# van_pro.net
KiCad netlist of a schematic drawn in EAGLE
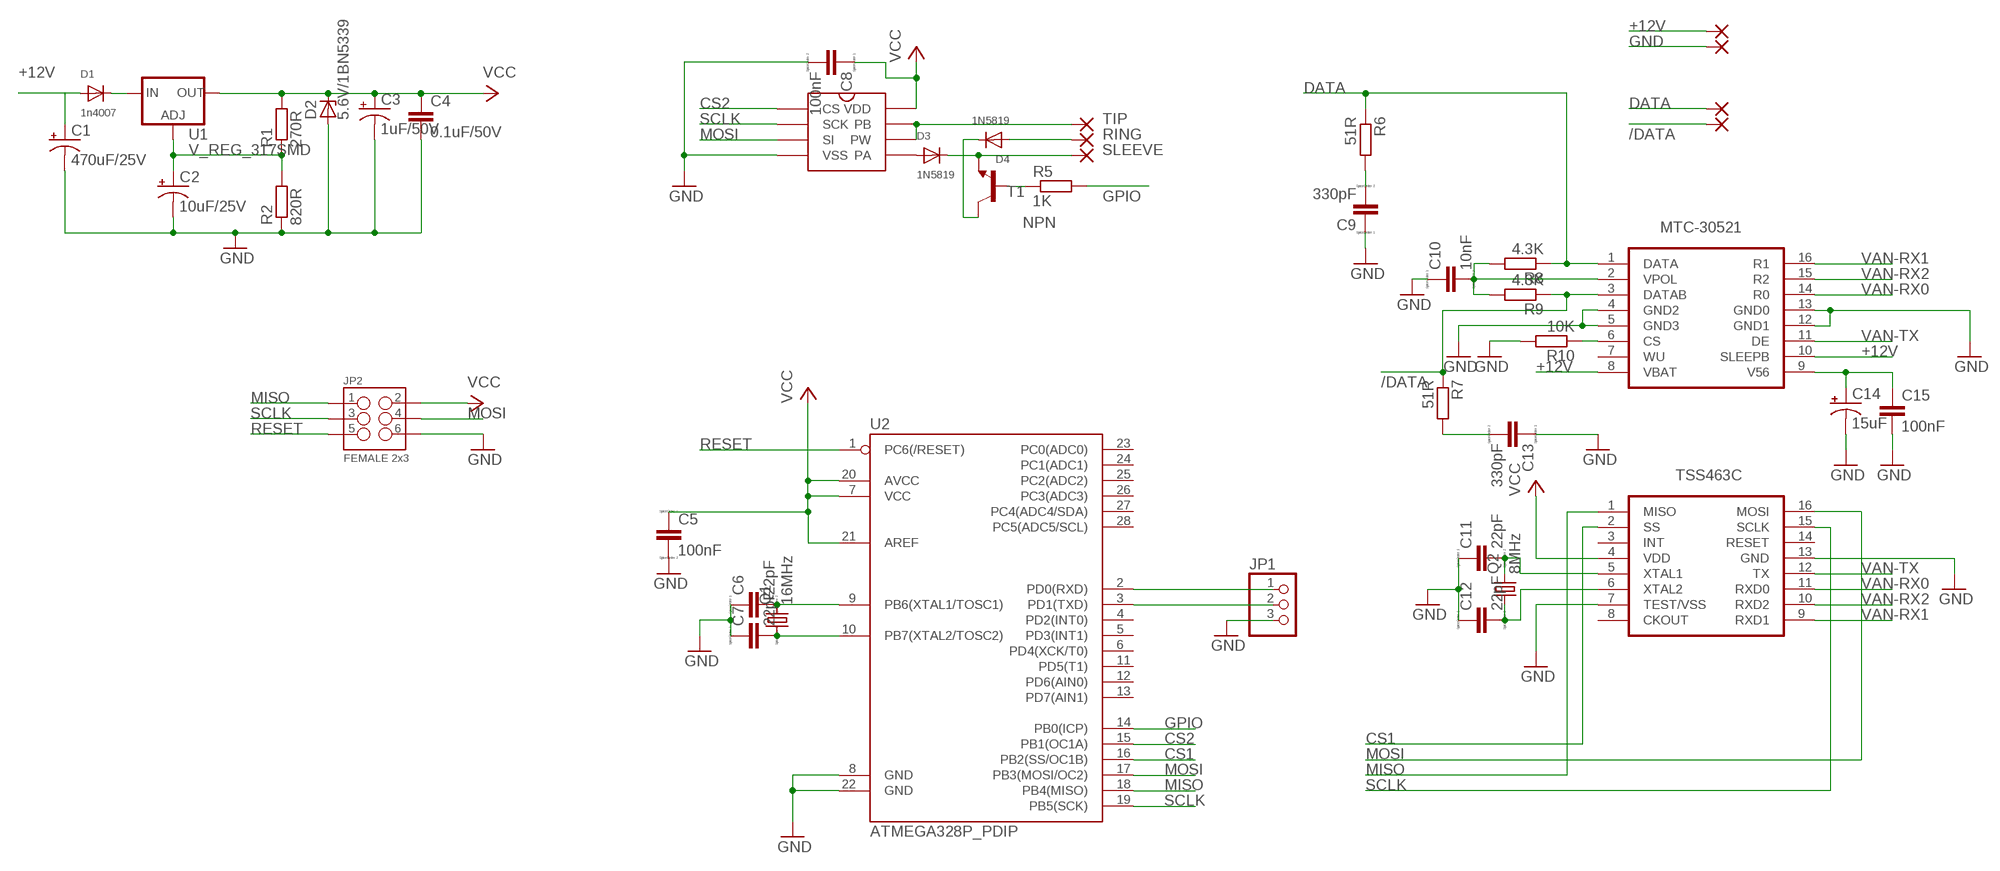
[diagram p0: schematic, sheet 1]

(export (version "E")
  (design (tool "Eeschema 10.0.6"))
  (components
    (comp (ref "/DATA")
      (value "WIREPAD2,54/0,8")
      (footprint "eagle-import:2,54_0,8")
      (libsource (lib "eagle-import") (part "WIREPAD2,54/0,8"))
    )
    (comp (ref "12V")
      (value "WIREPAD2,54/0,8")
      (footprint "eagle-import:2,54_0,8")
      (libsource (lib "eagle-import") (part "WIREPAD2,54/0,8"))
    )
    (comp (ref "C1")
      (value "470uF/25V")
      (footprint "eagle-import:E3,5-8")
      (libsource (lib "eagle-import") (part "CPOL-USE3.5-8"))
    )
    (comp (ref "C2")
      (value "10uF/25V")
      (footprint "eagle-import:E2-5")
      (libsource (lib "eagle-import") (part "CPOL-USE2-5"))
    )
    (comp (ref "C3")
      (value "1uF/50V")
      (footprint "eagle-import:E2-5")
      (libsource (lib "eagle-import") (part "CPOL-USE2-5"))
    )
    (comp (ref "C4")
      (value "0.1uF/50V")
      (footprint "eagle-import:C0805")
      (libsource (lib "eagle-import") (part "C-EUC0805"))
    )
    (comp (ref "C5")
      (value "100nF")
      (footprint "eagle-import:C0603")
      (libsource (lib "eagle-import") (part "CC0603"))
    )
    (comp (ref "C6")
      (value "22pF")
      (footprint "eagle-import:C0603")
      (fields (field (name "MF") "AVX") (field (name "MPN") "08052A220JAT2A"))
      (libsource (lib "eagle-import") (part "CC0603"))
    )
    (comp (ref "C7")
      (value "22pF")
      (footprint "eagle-import:C0603")
      (fields (field (name "MF") "AVX") (field (name "MPN") "08052A220JAT2A"))
      (libsource (lib "eagle-import") (part "CC0603"))
    )
    (comp (ref "C8")
      (value "100nF")
      (footprint "eagle-import:C0603")
      (libsource (lib "eagle-import") (part "CC0603"))
    )
    (comp (ref "C9")
      (value "330pF")
      (footprint "eagle-import:C0603")
      (fields (field (name "MF") "AVX") (field (name "MPN") "08052A220JAT2A"))
      (libsource (lib "eagle-import") (part "CC0603"))
    )
    (comp (ref "C10")
      (value "10nF")
      (footprint "eagle-import:C0603")
      (fields (field (name "MF") "AVX") (field (name "MPN") "08052A220JAT2A"))
      (libsource (lib "eagle-import") (part "CC0603"))
    )
    (comp (ref "C11")
      (value "22pF")
      (footprint "eagle-import:C0603")
      (fields (field (name "MF") "AVX") (field (name "MPN") "08052A220JAT2A"))
      (libsource (lib "eagle-import") (part "CC0603"))
    )
    (comp (ref "C12")
      (value "22pF")
      (footprint "eagle-import:C0603")
      (fields (field (name "MF") "AVX") (field (name "MPN") "08052A220JAT2A"))
      (libsource (lib "eagle-import") (part "CC0603"))
    )
    (comp (ref "C13")
      (value "330pF")
      (footprint "eagle-import:C0603")
      (fields (field (name "MF") "AVX") (field (name "MPN") "08052A220JAT2A"))
      (libsource (lib "eagle-import") (part "CC0603"))
    )
    (comp (ref "C14")
      (value "15uF")
      (footprint "eagle-import:EIA3216")
      (fields (field (name "MF") "AVX") (field (name "MPN") "08052A220JAT2A"))
      (libsource (lib "eagle-import") (part "10UF-16V-10%(TANT)"))
    )
    (comp (ref "C15")
      (value "100nF")
      (footprint "eagle-import:C1206")
      (fields (field (name "MF") "AVX") (field (name "MPN") "08052A220JAT2A"))
      (libsource (lib "eagle-import") (part "resistor_C-EUC1206"))
    )
    (comp (ref "D1")
      (value "1n4007")
      (footprint "eagle-import:SMADIODE")
      (libsource (lib "eagle-import") (part "DIODESMA"))
    )
    (comp (ref "D2")
      (value "5.6V/1BN5339")
      (footprint "eagle-import:DO41Z10")
      (libsource (lib "eagle-import") (part "ZENER-DIODEDO41Z10"))
    )
    (comp (ref "D3")
      (value "1N5819")
      (footprint "eagle-import:SMADIODE")
      (libsource (lib "eagle-import") (part "DIODESMA"))
    )
    (comp (ref "D4")
      (value "1N5819")
      (footprint "eagle-import:SMADIODE")
      (libsource (lib "eagle-import") (part "DIODESMA"))
    )
    (comp (ref "DATA")
      (value "WIREPAD2,54/0,8")
      (footprint "eagle-import:2,54_0,8")
      (libsource (lib "eagle-import") (part "WIREPAD2,54/0,8"))
    )
    (comp (ref "GND")
      (value "WIREPAD2,54/0,8")
      (footprint "eagle-import:2,54_0,8")
      (libsource (lib "eagle-import") (part "WIREPAD2,54/0,8"))
    )
    (comp (ref "IC1")
      (value "MCP41100")
      (footprint "eagle-import:SO8")
      (libsource (lib "eagle-import") (part "MCP41100"))
    )
    (comp (ref "IC2")
      (value "MTC-20521")
      (footprint "eagle-import:MTC-30521")
      (fields (field (name "MF") "MTC-30521"))
      (libsource (lib "eagle-import") (part "MTC-20521"))
    )
    (comp (ref "JP1")
      (value "PINHD-1X3")
      (footprint "eagle-import:1X03")
      (libsource (lib "eagle-import") (part "PINHD-1X3"))
    )
    (comp (ref "JP2")
      (value "FEMALE 2x3")
      (footprint "eagle-import:2X3")
      (libsource (lib "eagle-import") (part "M03X2FEMALE"))
    )
    (comp (ref "Q1")
      (value "16MHz")
      (footprint "eagle-import:HC49UP")
      (fields (field (name "MF") "MULTICOMP") (field (name "MPN") "HC49SM-3.6864-30-50-60-16-ATF"))
      (libsource (lib "eagle-import") (part "CRYSTALHC49UP"))
    )
    (comp (ref "Q2")
      (value "8MHz")
      (footprint "eagle-import:HC49UP")
      (fields (field (name "MF") "MULTICOMP") (field (name "MPN") "HC49SM-3.6864-30-50-60-16-ATF"))
      (libsource (lib "eagle-import") (part "CRYSTALHC49UP"))
    )
    (comp (ref "R1")
      (value "270R")
      (footprint "eagle-import:R0805")
      (libsource (lib "eagle-import") (part "R-EU_R0805"))
    )
    (comp (ref "R2")
      (value "820R")
      (footprint "eagle-import:R0805")
      (libsource (lib "eagle-import") (part "R-EU_R0805"))
    )
    (comp (ref "R5")
      (value "1K")
      (footprint "eagle-import:R0603")
      (libsource (lib "eagle-import") (part "resistor_R-EU_R0603"))
    )
    (comp (ref "R6")
      (value "51R")
      (footprint "eagle-import:R0603")
      (libsource (lib "eagle-import") (part "resistor_R-EU_R0603"))
    )
    (comp (ref "R7")
      (value "51R")
      (footprint "eagle-import:R0603")
      (libsource (lib "eagle-import") (part "resistor_R-EU_R0603"))
    )
    (comp (ref "R8")
      (value "4.3K")
      (footprint "eagle-import:R0603")
      (libsource (lib "eagle-import") (part "resistor_R-EU_R0603"))
    )
    (comp (ref "R9")
      (value "4.3K")
      (footprint "eagle-import:R0603")
      (libsource (lib "eagle-import") (part "resistor_R-EU_R0603"))
    )
    (comp (ref "R10")
      (value "10K")
      (footprint "eagle-import:R0603")
      (libsource (lib "eagle-import") (part "resistor_R-EU_R0603"))
    )
    (comp (ref "RNG")
      (value "1,6/0,8")
      (footprint "eagle-import:1,6_0,8")
      (libsource (lib "eagle-import") (part "1,6/0,8"))
    )
    (comp (ref "SL")
      (value "1,6/0,8")
      (footprint "eagle-import:1,6_0,8")
      (libsource (lib "eagle-import") (part "1,6/0,8"))
    )
    (comp (ref "T1")
      (value "NPN")
      (footprint "eagle-import:SOT23-EBC")
      (libsource (lib "eagle-import") (part "-NPN-SOT23-EBC"))
    )
    (comp (ref "TIP")
      (value "1,6/0,8")
      (footprint "eagle-import:1,6_0,8")
      (libsource (lib "eagle-import") (part "1,6/0,8"))
    )
    (comp (ref "U1")
      (value "V_REG_317SMD")
      (footprint "eagle-import:SOT223")
      (libsource (lib "eagle-import") (part "V_REG_317SMD"))
    )
    (comp (ref "U2")
      (value "ATMEGA328P_PDIP")
      (footprint "eagle-import:DIL28-3")
      (libsource (lib "eagle-import") (part "ATMEGA328P_PDIP"))
    )
    (comp (ref "VAN1")
      (value "TSS463C")
      (footprint "eagle-import:TSS463C")
      (fields (field (name "MF") "TSS463C"))
      (libsource (lib "eagle-import") (part "TSS463C"))
    )
  )
  (nets
    (net (code "1") (name "/+12V") (class "Default")
      (node (ref "12V") (pin "1") (pinfunction "P_1") (pintype "passive"))
      (node (ref "C1") (pin "+") (pinfunction "+_+") (pintype "passive"))
      (node (ref "D1") (pin "A") (pinfunction "A_A") (pintype "passive"))
      (node (ref "IC2") (pin "10") (pinfunction "SLEEPB_10") (pintype "bidirectional"))
      (node (ref "IC2") (pin "8") (pinfunction "VBAT_8") (pintype "power_in"))
    )
    (net (code "2") (name "/CS1") (class "Default")
      (node (ref "U2") (pin "16") (pinfunction "PB2(SS/OC1B)_16") (pintype "bidirectional"))
      (node (ref "VAN1") (pin "2") (pinfunction "SS_2") (pintype "bidirectional"))
    )
    (net (code "3") (name "/CS2") (class "Default")
      (node (ref "IC1") (pin "1") (pinfunction "CS_1") (pintype "input"))
      (node (ref "U2") (pin "15") (pinfunction "PB1(OC1A)_15") (pintype "bidirectional"))
    )
    (net (code "4") (name "/DATA") (class "Default")
      (node (ref "DATA") (pin "1") (pinfunction "P_1") (pintype "passive"))
      (node (ref "IC2") (pin "1") (pinfunction "DATA_1") (pintype "bidirectional"))
      (node (ref "R6") (pin "1") (pinfunction "1_1") (pintype "passive"))
      (node (ref "R8") (pin "1") (pinfunction "1_1") (pintype "passive"))
    )
    (net (code "5") (name "/GPIO") (class "Default")
      (node (ref "R5") (pin "2") (pinfunction "2_2") (pintype "passive"))
      (node (ref "U2") (pin "14") (pinfunction "PB0(ICP)_14") (pintype "bidirectional"))
    )
    (net (code "6") (name "/MISO") (class "Default")
      (node (ref "JP2") (pin "1") (pinfunction "1_1") (pintype "bidirectional"))
      (node (ref "U2") (pin "18") (pinfunction "PB4(MISO)_18") (pintype "bidirectional"))
      (node (ref "VAN1") (pin "1") (pinfunction "MISO_1") (pintype "bidirectional"))
    )
    (net (code "7") (name "/MOSI") (class "Default")
      (node (ref "IC1") (pin "3") (pinfunction "SI_3") (pintype "bidirectional"))
      (node (ref "JP2") (pin "4") (pinfunction "4_4") (pintype "bidirectional"))
      (node (ref "U2") (pin "17") (pinfunction "PB3(MOSI/OC2)_17") (pintype "bidirectional"))
      (node (ref "VAN1") (pin "16") (pinfunction "MOSI_16") (pintype "bidirectional"))
    )
    (net (code "8") (name "/RESET") (class "Default")
      (node (ref "JP2") (pin "5") (pinfunction "5_5") (pintype "bidirectional"))
      (node (ref "U2") (pin "1") (pinfunction "PC6(/RESET)_1") (pintype "bidirectional"))
    )
    (net (code "9") (name "/RING") (class "Default")
      (node (ref "D4") (pin "A") (pinfunction "A_A") (pintype "passive"))
      (node (ref "RNG") (pin "1") (pinfunction "P_1") (pintype "passive"))
    )
    (net (code "10") (name "/SCLK") (class "Default")
      (node (ref "IC1") (pin "2") (pinfunction "SCK_2") (pintype "input"))
      (node (ref "JP2") (pin "3") (pinfunction "3_3") (pintype "bidirectional"))
      (node (ref "U2") (pin "19") (pinfunction "PB5(SCK)_19") (pintype "bidirectional"))
      (node (ref "VAN1") (pin "15") (pinfunction "SCLK_15") (pintype "bidirectional"))
    )
    (net (code "11") (name "/SLEEVE") (class "Default")
      (node (ref "D3") (pin "C") (pinfunction "C_C") (pintype "passive"))
      (node (ref "SL") (pin "1") (pinfunction "P_1") (pintype "passive"))
      (node (ref "T1") (pin "E") (pinfunction "E_E") (pintype "passive"))
    )
    (net (code "12") (name "/TIP") (class "Default")
      (node (ref "IC1") (pin "6") (pinfunction "PW_6") (pintype "bidirectional"))
      (node (ref "IC1") (pin "7") (pinfunction "PB_7") (pintype "bidirectional"))
      (node (ref "TIP") (pin "1") (pinfunction "P_1") (pintype "passive"))
    )
    (net (code "13") (name "/VAN-RX0") (class "Default")
      (node (ref "IC2") (pin "14") (pinfunction "R0_14") (pintype "bidirectional"))
      (node (ref "VAN1") (pin "11") (pinfunction "RXD0_11") (pintype "bidirectional"))
    )
    (net (code "14") (name "/VAN-RX1") (class "Default")
      (node (ref "IC2") (pin "16") (pinfunction "R1_16") (pintype "bidirectional"))
      (node (ref "VAN1") (pin "9") (pinfunction "RXD1_9") (pintype "bidirectional"))
    )
    (net (code "15") (name "/VAN-RX2") (class "Default")
      (node (ref "IC2") (pin "15") (pinfunction "R2_15") (pintype "bidirectional"))
      (node (ref "VAN1") (pin "10") (pinfunction "RXD2_10") (pintype "bidirectional"))
    )
    (net (code "16") (name "/VAN-TX") (class "Default")
      (node (ref "IC2") (pin "11") (pinfunction "DE_11") (pintype "bidirectional"))
      (node (ref "VAN1") (pin "12") (pinfunction "TX_12") (pintype "bidirectional"))
    )
    (net (code "17") (name "/{slash}DATA") (class "Default")
      (node (ref "/DATA") (pin "1") (pinfunction "P_1") (pintype "passive"))
      (node (ref "IC2") (pin "3") (pinfunction "DATAB_3") (pintype "bidirectional"))
      (node (ref "R7") (pin "1") (pinfunction "1_1") (pintype "passive"))
      (node (ref "R9") (pin "1") (pinfunction "1_1") (pintype "passive"))
    )
    (net (code "18") (name "GND") (class "Default")
      (node (ref "C1") (pin "-") (pinfunction "-_-") (pintype "passive"))
      (node (ref "C10") (pin "1") (pinfunction "1_1") (pintype "passive"))
      (node (ref "C11") (pin "1") (pinfunction "1_1") (pintype "passive"))
      (node (ref "C12") (pin "1") (pinfunction "1_1") (pintype "passive"))
      (node (ref "C13") (pin "1") (pinfunction "1_1") (pintype "passive"))
      (node (ref "C14") (pin "C") (pinfunction "-_C") (pintype "passive"))
      (node (ref "C15") (pin "2") (pinfunction "2_2") (pintype "passive"))
      (node (ref "C2") (pin "-") (pinfunction "-_-") (pintype "passive"))
      (node (ref "C3") (pin "-") (pinfunction "-_-") (pintype "passive"))
      (node (ref "C4") (pin "2") (pinfunction "2_2") (pintype "passive"))
      (node (ref "C5") (pin "2") (pinfunction "2_2") (pintype "passive"))
      (node (ref "C6") (pin "1") (pinfunction "1_1") (pintype "passive"))
      (node (ref "C7") (pin "1") (pinfunction "1_1") (pintype "passive"))
      (node (ref "C8") (pin "2") (pinfunction "2_2") (pintype "passive"))
      (node (ref "C9") (pin "1") (pinfunction "1_1") (pintype "passive"))
      (node (ref "D2") (pin "A") (pinfunction "A_A") (pintype "passive"))
      (node (ref "GND") (pin "1") (pinfunction "P_1") (pintype "passive"))
      (node (ref "IC1") (pin "4") (pinfunction "VSS_4") (pintype "power_in"))
      (node (ref "IC2") (pin "12") (pinfunction "GND1_12") (pintype "power_in"))
      (node (ref "IC2") (pin "13") (pinfunction "GND0_13") (pintype "power_in"))
      (node (ref "IC2") (pin "4") (pinfunction "GND2_4") (pintype "power_in"))
      (node (ref "IC2") (pin "5") (pinfunction "GND3_5") (pintype "power_in"))
      (node (ref "JP1") (pin "3") (pinfunction "3_3") (pintype "passive"))
      (node (ref "JP2") (pin "6") (pinfunction "6_6") (pintype "bidirectional"))
      (node (ref "R10") (pin "2") (pinfunction "2_2") (pintype "passive"))
      (node (ref "R2") (pin "1") (pinfunction "1_1") (pintype "passive"))
      (node (ref "U2") (pin "22") (pinfunction "GND_22") (pintype "bidirectional"))
      (node (ref "U2") (pin "8") (pinfunction "GND_8") (pintype "bidirectional"))
      (node (ref "VAN1") (pin "13") (pinfunction "GND_13") (pintype "bidirectional"))
      (node (ref "VAN1") (pin "7") (pinfunction "TEST/VSS_7") (pintype "bidirectional"))
    )
    (net (code "19") (name "Net-(C9-Pad2)") (class "Default")
      (node (ref "C9") (pin "2") (pinfunction "2_2") (pintype "passive"))
      (node (ref "R6") (pin "2") (pinfunction "2_2") (pintype "passive"))
    )
    (net (code "20") (name "Net-(C13-Pad2)") (class "Default")
      (node (ref "C13") (pin "2") (pinfunction "2_2") (pintype "passive"))
      (node (ref "R7") (pin "2") (pinfunction "2_2") (pintype "passive"))
    )
    (net (code "21") (name "Net-(C14-+)") (class "Default")
      (node (ref "C14") (pin "A") (pinfunction "+_A") (pintype "passive"))
      (node (ref "C15") (pin "1") (pinfunction "1_1") (pintype "passive"))
      (node (ref "IC2") (pin "9") (pinfunction "V56_9") (pintype "power_in"))
    )
    (net (code "22") (name "Net-(D4-PadC)") (class "Default")
      (node (ref "D4") (pin "C") (pinfunction "C_C") (pintype "passive"))
      (node (ref "T1") (pin "C") (pinfunction "C_C") (pintype "passive"))
    )
    (net (code "23") (name "Net-(IC1-PA)") (class "Default")
      (node (ref "D3") (pin "A") (pinfunction "A_A") (pintype "passive"))
      (node (ref "IC1") (pin "5") (pinfunction "PA_5") (pintype "bidirectional"))
    )
    (net (code "24") (name "Net-(IC2-CS)") (class "Default")
      (node (ref "IC2") (pin "6") (pinfunction "CS_6") (pintype "bidirectional"))
      (node (ref "R10") (pin "1") (pinfunction "1_1") (pintype "passive"))
    )
    (net (code "25") (name "Net-(IC2-VPOL)") (class "Default")
      (node (ref "C10") (pin "2") (pinfunction "2_2") (pintype "passive"))
      (node (ref "IC2") (pin "2") (pinfunction "VPOL_2") (pintype "bidirectional"))
      (node (ref "R8") (pin "2") (pinfunction "2_2") (pintype "passive"))
      (node (ref "R9") (pin "2") (pinfunction "2_2") (pintype "passive"))
    )
    (net (code "26") (name "Net-(R5-Pad1)") (class "Default")
      (node (ref "R5") (pin "1") (pinfunction "1_1") (pintype "passive"))
      (node (ref "T1") (pin "B") (pinfunction "B_B") (pintype "passive"))
    )
    (net (code "27") (name "Net-(U1-ADJ)") (class "Default")
      (node (ref "C2") (pin "+") (pinfunction "+_+") (pintype "passive"))
      (node (ref "R1") (pin "1") (pinfunction "1_1") (pintype "passive"))
      (node (ref "R2") (pin "2") (pinfunction "2_2") (pintype "passive"))
      (node (ref "U1") (pin "1") (pinfunction "ADJ_1") (pintype "input"))
    )
    (net (code "28") (name "Net-(U1-IN)") (class "Default")
      (node (ref "D1") (pin "C") (pinfunction "C_C") (pintype "passive"))
      (node (ref "U1") (pin "3") (pinfunction "IN_3") (pintype "input"))
    )
    (net (code "29") (name "Net-(U2-PB6(XTAL1{slash}TOSC1))") (class "Default")
      (node (ref "C6") (pin "2") (pinfunction "2_2") (pintype "passive"))
      (node (ref "Q1") (pin "2") (pinfunction "2_2") (pintype "passive"))
      (node (ref "U2") (pin "9") (pinfunction "PB6(XTAL1/TOSC1)_9") (pintype "bidirectional"))
    )
    (net (code "30") (name "Net-(U2-PB7(XTAL2{slash}TOSC2))") (class "Default")
      (node (ref "C7") (pin "2") (pinfunction "2_2") (pintype "passive"))
      (node (ref "Q1") (pin "1") (pinfunction "1_1") (pintype "passive"))
      (node (ref "U2") (pin "10") (pinfunction "PB7(XTAL2/TOSC2)_10") (pintype "bidirectional"))
    )
    (net (code "31") (name "Net-(U2-PD0(RXD))") (class "Default")
      (node (ref "JP1") (pin "1") (pinfunction "1_1") (pintype "passive"))
      (node (ref "U2") (pin "2") (pinfunction "PD0(RXD)_2") (pintype "bidirectional"))
    )
    (net (code "32") (name "Net-(U2-PD1(TXD))") (class "Default")
      (node (ref "JP1") (pin "2") (pinfunction "2_2") (pintype "passive"))
      (node (ref "U2") (pin "3") (pinfunction "PD1(TXD)_3") (pintype "bidirectional"))
    )
    (net (code "33") (name "Net-(VAN1-XTAL1)") (class "Default")
      (node (ref "C11") (pin "2") (pinfunction "2_2") (pintype "passive"))
      (node (ref "Q2") (pin "2") (pinfunction "2_2") (pintype "passive"))
      (node (ref "VAN1") (pin "5") (pinfunction "XTAL1_5") (pintype "bidirectional"))
    )
    (net (code "34") (name "Net-(VAN1-XTAL2)") (class "Default")
      (node (ref "C12") (pin "2") (pinfunction "2_2") (pintype "passive"))
      (node (ref "Q2") (pin "1") (pinfunction "1_1") (pintype "passive"))
      (node (ref "VAN1") (pin "6") (pinfunction "XTAL2_6") (pintype "bidirectional"))
    )
    (net (code "35") (name "VCC") (class "Default")
      (node (ref "C3") (pin "+") (pinfunction "+_+") (pintype "passive"))
      (node (ref "C4") (pin "1") (pinfunction "1_1") (pintype "passive"))
      (node (ref "C5") (pin "1") (pinfunction "1_1") (pintype "passive"))
      (node (ref "C8") (pin "1") (pinfunction "1_1") (pintype "passive"))
      (node (ref "D2") (pin "C") (pinfunction "C_C") (pintype "passive"))
      (node (ref "IC1") (pin "8") (pinfunction "VDD_8") (pintype "power_in"))
      (node (ref "JP2") (pin "2") (pinfunction "2_2") (pintype "bidirectional"))
      (node (ref "R1") (pin "2") (pinfunction "2_2") (pintype "passive"))
      (node (ref "U1") (pin "2") (pinfunction "OUT_2") (pintype "output"))
      (node (ref "U2") (pin "20") (pinfunction "AVCC_20") (pintype "bidirectional"))
      (node (ref "U2") (pin "21") (pinfunction "AREF_21") (pintype "bidirectional"))
      (node (ref "U2") (pin "7") (pinfunction "VCC_7") (pintype "bidirectional"))
      (node (ref "VAN1") (pin "4") (pinfunction "VDD_4") (pintype "power_in"))
    )
    (net (code "36") (name "unconnected-(IC2-WU-Pad7)") (class "Default")
      (node (ref "IC2") (pin "7") (pinfunction "WU_7") (pintype "bidirectional"))
    )
    (net (code "37") (name "unconnected-(U2-PC0(ADC0)-Pad23)") (class "Default")
      (node (ref "U2") (pin "23") (pinfunction "PC0(ADC0)_23") (pintype "bidirectional"))
    )
    (net (code "38") (name "unconnected-(U2-PC1(ADC1)-Pad24)") (class "Default")
      (node (ref "U2") (pin "24") (pinfunction "PC1(ADC1)_24") (pintype "bidirectional"))
    )
    (net (code "39") (name "unconnected-(U2-PC2(ADC2)-Pad25)") (class "Default")
      (node (ref "U2") (pin "25") (pinfunction "PC2(ADC2)_25") (pintype "bidirectional"))
    )
    (net (code "40") (name "unconnected-(U2-PC3(ADC3)-Pad26)") (class "Default")
      (node (ref "U2") (pin "26") (pinfunction "PC3(ADC3)_26") (pintype "bidirectional"))
    )
    (net (code "41") (name "unconnected-(U2-PC4(ADC4{slash}SDA)-Pad27)") (class "Default")
      (node (ref "U2") (pin "27") (pinfunction "PC4(ADC4/SDA)_27") (pintype "bidirectional"))
    )
    (net (code "42") (name "unconnected-(U2-PC5(ADC5{slash}SCL)-Pad28)") (class "Default")
      (node (ref "U2") (pin "28") (pinfunction "PC5(ADC5/SCL)_28") (pintype "bidirectional"))
    )
    (net (code "43") (name "unconnected-(U2-PD2(INT0)-Pad4)") (class "Default")
      (node (ref "U2") (pin "4") (pinfunction "PD2(INT0)_4") (pintype "bidirectional"))
    )
    (net (code "44") (name "unconnected-(U2-PD3(INT1)-Pad5)") (class "Default")
      (node (ref "U2") (pin "5") (pinfunction "PD3(INT1)_5") (pintype "bidirectional"))
    )
    (net (code "45") (name "unconnected-(U2-PD4(XCK{slash}T0)-Pad6)") (class "Default")
      (node (ref "U2") (pin "6") (pinfunction "PD4(XCK/T0)_6") (pintype "bidirectional"))
    )
    (net (code "46") (name "unconnected-(U2-PD5(T1)-Pad11)") (class "Default")
      (node (ref "U2") (pin "11") (pinfunction "PD5(T1)_11") (pintype "bidirectional"))
    )
    (net (code "47") (name "unconnected-(U2-PD6(AIN0)-Pad12)") (class "Default")
      (node (ref "U2") (pin "12") (pinfunction "PD6(AIN0)_12") (pintype "bidirectional"))
    )
    (net (code "48") (name "unconnected-(U2-PD7(AIN1)-Pad13)") (class "Default")
      (node (ref "U2") (pin "13") (pinfunction "PD7(AIN1)_13") (pintype "bidirectional"))
    )
    (net (code "49") (name "unconnected-(VAN1-CKOUT-Pad8)") (class "Default")
      (node (ref "VAN1") (pin "8") (pinfunction "CKOUT_8") (pintype "bidirectional"))
    )
    (net (code "50") (name "unconnected-(VAN1-INT-Pad3)") (class "Default")
      (node (ref "VAN1") (pin "3") (pinfunction "INT_3") (pintype "bidirectional"))
    )
    (net (code "51") (name "unconnected-(VAN1-RESET-Pad14)") (class "Default")
      (node (ref "VAN1") (pin "14") (pinfunction "RESET_14") (pintype "bidirectional"))
    )
  )
)
